# GL3520.net
KiCad netlist of a schematic drawn in Altium Designer
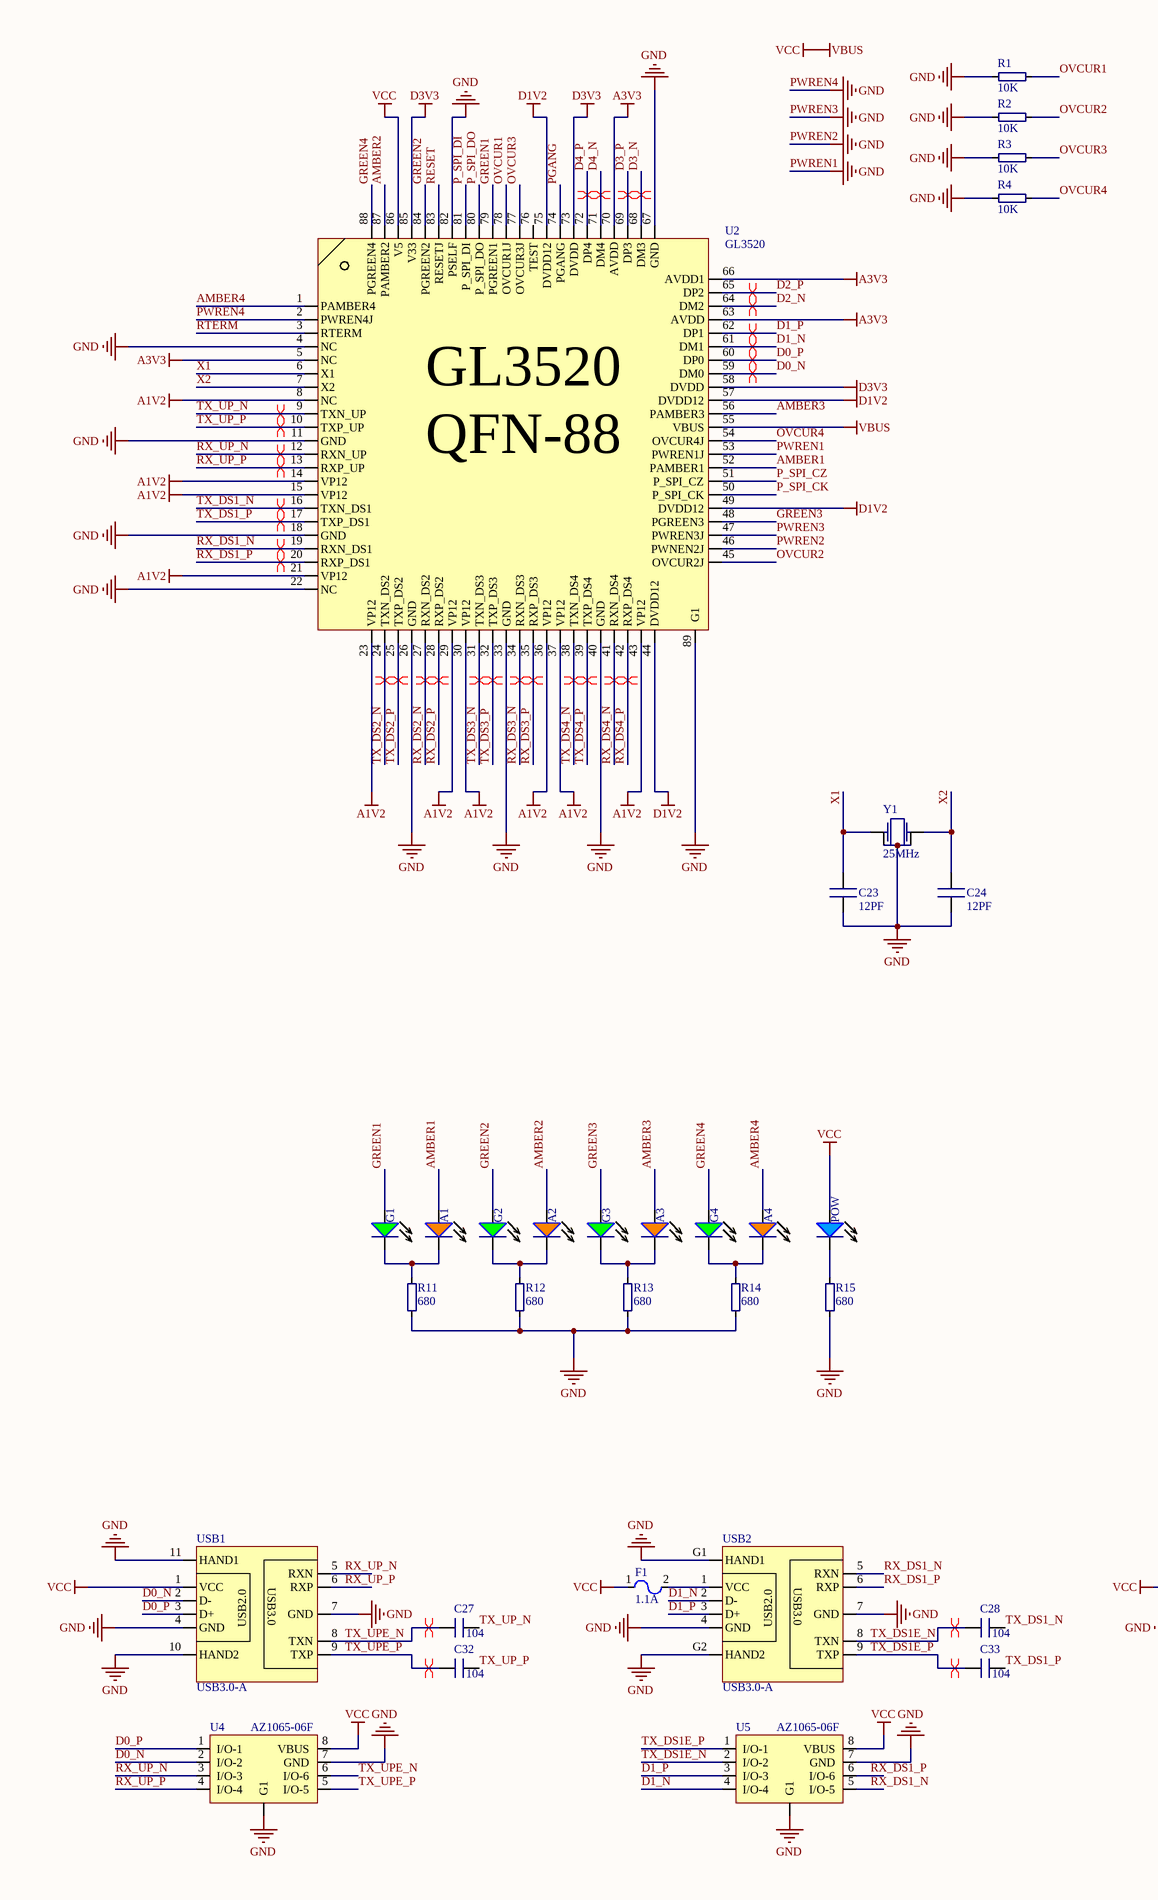
[diagram p0: GL3520.SchDoc, left]
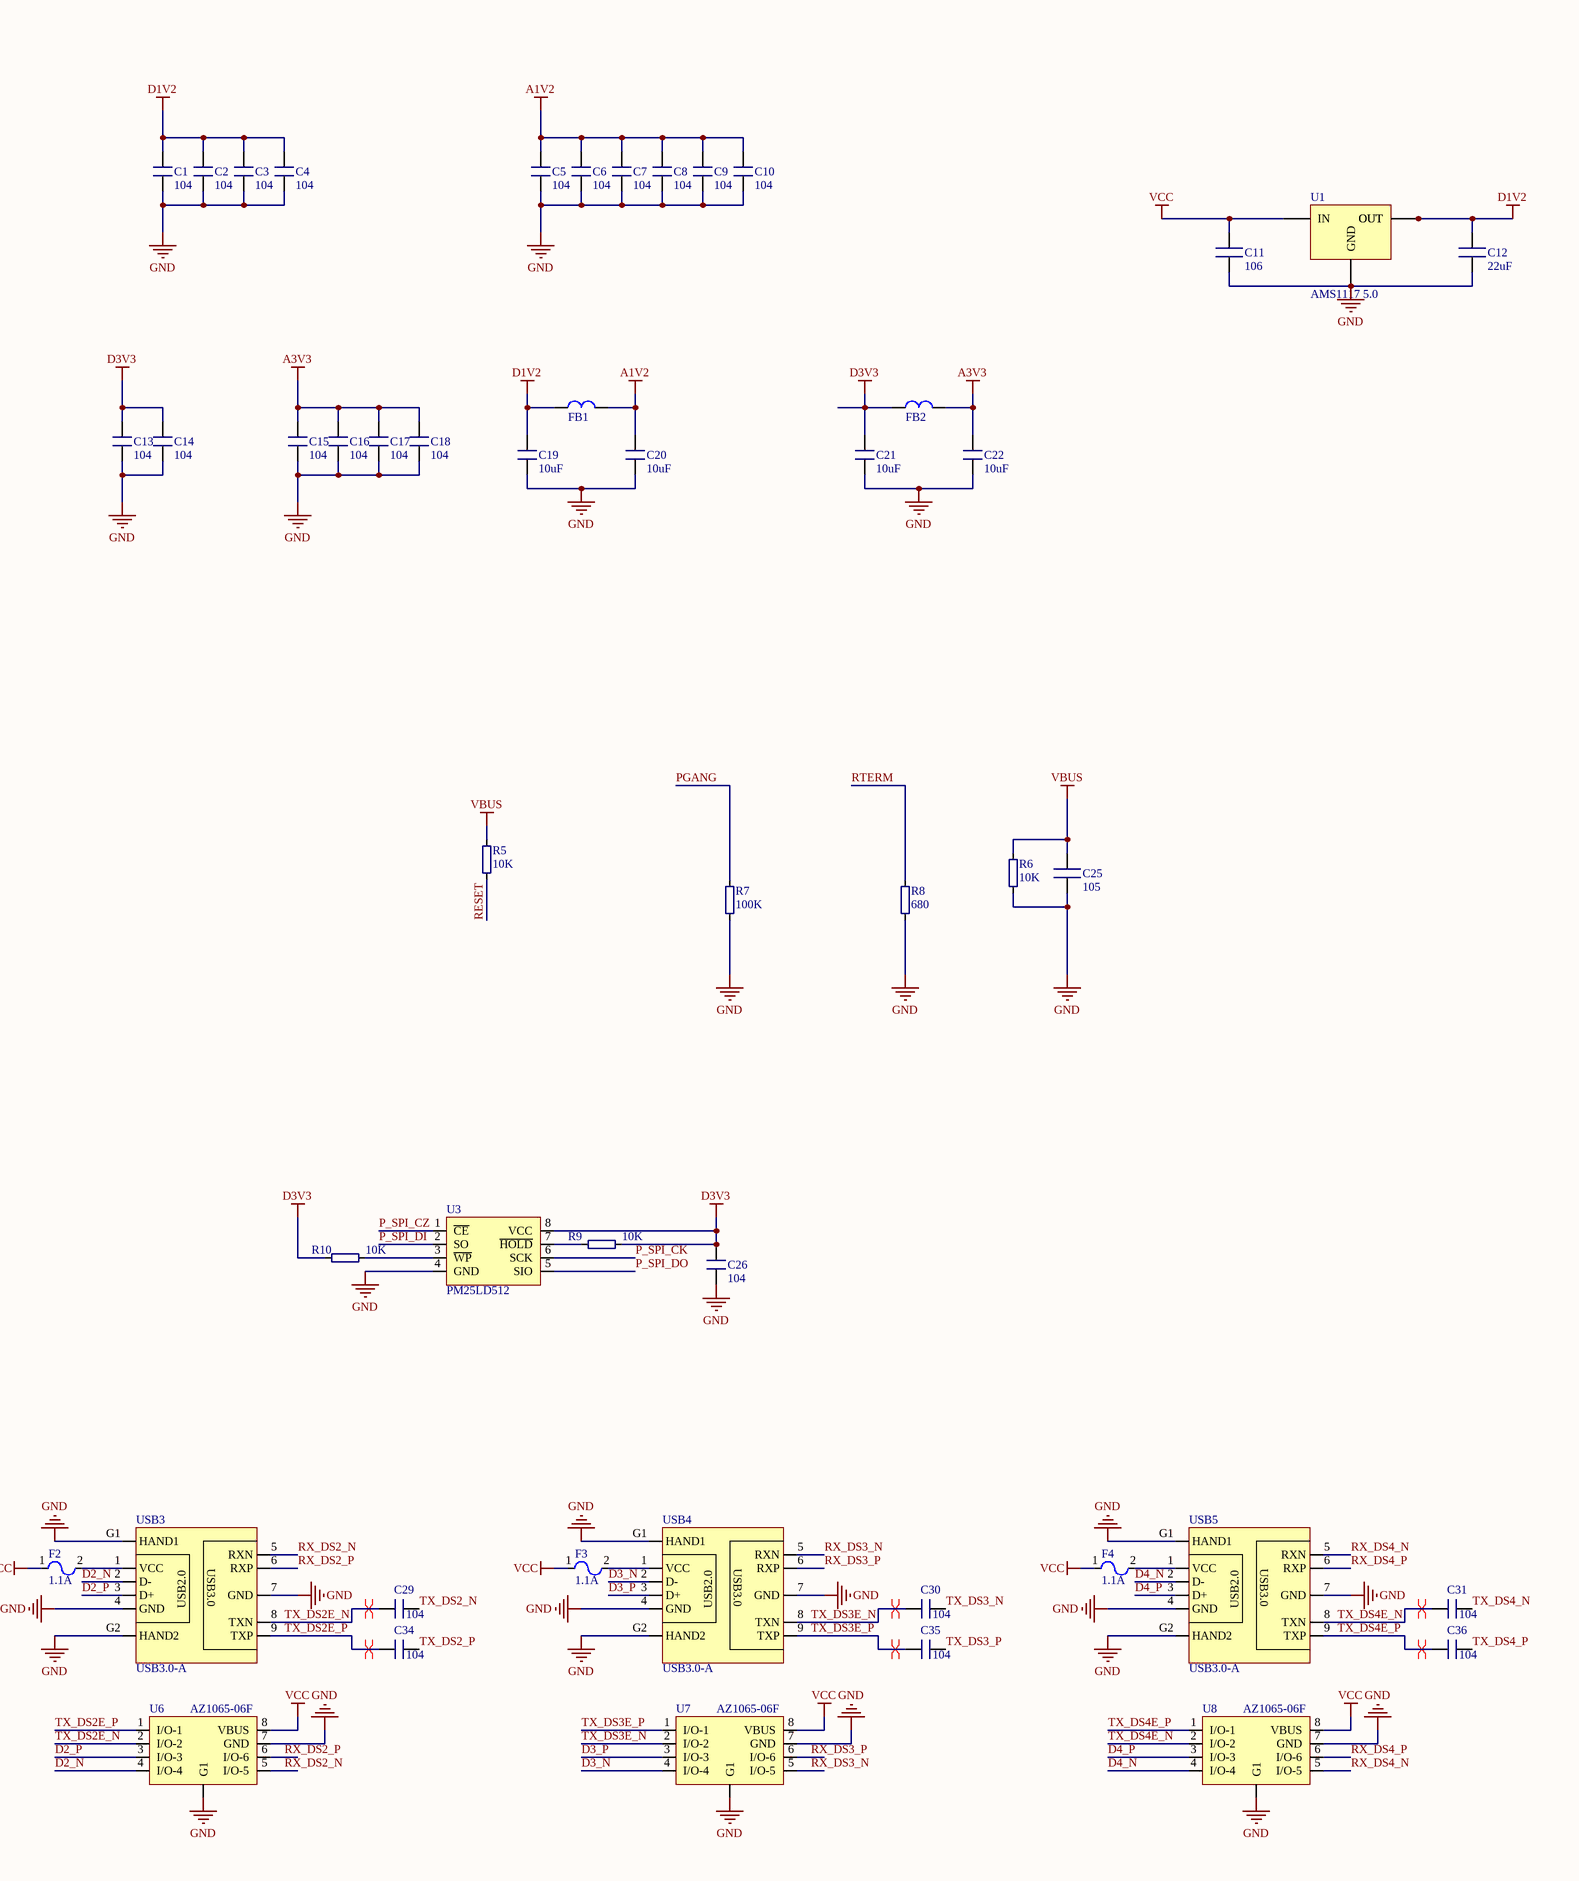
[diagram p1: GL3520.SchDoc, right]

(export (version "E")
  (design (tool "Eeschema 10.0.6"))
  (components
    (comp (ref "A1")
      (value "SMD-LED_Orige")
      (footprint "SMD-LED-0805Y")
      (libsource (lib "arduino") (part "SMD-LED_Orige"))
    )
    (comp (ref "A2")
      (value "SMD-LED_Orige")
      (footprint "SMD-LED-0805Y")
      (libsource (lib "arduino") (part "SMD-LED_Orige"))
    )
    (comp (ref "A3")
      (value "SMD-LED_Orige")
      (footprint "SMD-LED-0805Y")
      (libsource (lib "arduino") (part "SMD-LED_Orige"))
    )
    (comp (ref "A4")
      (value "SMD-LED_Orige")
      (footprint "SMD-LED-0805Y")
      (libsource (lib "arduino") (part "SMD-LED_Orige"))
    )
    (comp (ref "C1") (value "104") (footprint "SMD-C-0201") (libsource (lib "arduino") (part "SMD-C-0201")))
    (comp (ref "C2") (value "104") (footprint "SMD-C-0201") (libsource (lib "arduino") (part "SMD-C-0201")))
    (comp (ref "C3") (value "104") (footprint "SMD-C-0201") (libsource (lib "arduino") (part "SMD-C-0201")))
    (comp (ref "C4") (value "104") (footprint "SMD-C-0201") (libsource (lib "arduino") (part "SMD-C-0201")))
    (comp (ref "C5") (value "104") (footprint "SMD-C-0201") (libsource (lib "arduino") (part "SMD-C-0201")))
    (comp (ref "C6") (value "104") (footprint "SMD-C-0201") (libsource (lib "arduino") (part "SMD-C-0201")))
    (comp (ref "C7") (value "104") (footprint "SMD-C-0201") (libsource (lib "arduino") (part "SMD-C-0201")))
    (comp (ref "C8") (value "104") (footprint "SMD-C-0201") (libsource (lib "arduino") (part "SMD-C-0201")))
    (comp (ref "C9") (value "104") (footprint "SMD-C-0201") (libsource (lib "arduino") (part "SMD-C-0201")))
    (comp (ref "C10") (value "104") (footprint "SMD-C-0201") (libsource (lib "arduino") (part "SMD-C-0201")))
    (comp (ref "C11")
      (value "106")
      (footprint "SMD-C-0805")
      (fields (field (name "Comment") "SMD-C-0805"))
      (libsource (lib "") (part "SMD-C-0805_1"))
    )
    (comp (ref "C12")
      (value "22uF")
      (footprint "SMD-C-0805")
      (fields (field (name "Comment") "SMD-C-0805"))
      (libsource (lib "") (part "SMD-C-0805_1"))
    )
    (comp (ref "C13") (value "104") (footprint "SMD-C-0201") (libsource (lib "arduino") (part "SMD-C-0201")))
    (comp (ref "C14") (value "104") (footprint "SMD-C-0201") (libsource (lib "arduino") (part "SMD-C-0201")))
    (comp (ref "C15") (value "104") (footprint "SMD-C-0201") (libsource (lib "arduino") (part "SMD-C-0201")))
    (comp (ref "C16") (value "104") (footprint "SMD-C-0201") (libsource (lib "arduino") (part "SMD-C-0201")))
    (comp (ref "C17") (value "104") (footprint "SMD-C-0201") (libsource (lib "arduino") (part "SMD-C-0201")))
    (comp (ref "C18") (value "104") (footprint "SMD-C-0201") (libsource (lib "arduino") (part "SMD-C-0201")))
    (comp (ref "C19")
      (value "10uF")
      (footprint "SMD-C-0805")
      (description "贴片瓷片电容")
      (libsource (lib "arduino") (part "SMD-C-0805"))
    )
    (comp (ref "C20")
      (value "10uF")
      (footprint "SMD-C-0805")
      (description "贴片瓷片电容")
      (libsource (lib "arduino") (part "SMD-C-0805"))
    )
    (comp (ref "C21")
      (value "10uF")
      (footprint "SMD-C-0805")
      (description "贴片瓷片电容")
      (libsource (lib "arduino") (part "SMD-C-0805"))
    )
    (comp (ref "C22")
      (value "10uF")
      (footprint "SMD-C-0805")
      (description "贴片瓷片电容")
      (libsource (lib "arduino") (part "SMD-C-0805"))
    )
    (comp (ref "C23")
      (value "12PF")
      (footprint "SMD-C-0805")
      (fields (field (name "Comment") "SMD-C-0805"))
      (libsource (lib "") (part "SMD-C-0805_1"))
    )
    (comp (ref "C24")
      (value "12PF")
      (footprint "SMD-C-0805")
      (fields (field (name "Comment") "SMD-C-0805"))
      (libsource (lib "") (part "SMD-C-0805_1"))
    )
    (comp (ref "C25")
      (value "105")
      (footprint "SMD-C-0805")
      (fields (field (name "Comment") "SMD-C-0805"))
      (libsource (lib "") (part "SMD-C-0805_1"))
    )
    (comp (ref "C26")
      (value "104")
      (footprint "SMD-C-0805")
      (description "贴片瓷片电容")
      (libsource (lib "arduino") (part "SMD-C-0805"))
    )
    (comp (ref "C27") (value "104") (footprint "SMD-C-0201") (libsource (lib "arduino") (part "SMD-C-0201")))
    (comp (ref "C28") (value "104") (footprint "SMD-C-0201") (libsource (lib "arduino") (part "SMD-C-0201")))
    (comp (ref "C29") (value "104") (footprint "SMD-C-0201") (libsource (lib "arduino") (part "SMD-C-0201")))
    (comp (ref "C30") (value "104") (footprint "SMD-C-0201") (libsource (lib "arduino") (part "SMD-C-0201")))
    (comp (ref "C31") (value "104") (footprint "SMD-C-0201") (libsource (lib "arduino") (part "SMD-C-0201")))
    (comp (ref "C32") (value "104") (footprint "SMD-C-0201") (libsource (lib "arduino") (part "SMD-C-0201")))
    (comp (ref "C33") (value "104") (footprint "SMD-C-0201") (libsource (lib "arduino") (part "SMD-C-0201")))
    (comp (ref "C34") (value "104") (footprint "SMD-C-0201") (libsource (lib "arduino") (part "SMD-C-0201")))
    (comp (ref "C35") (value "104") (footprint "SMD-C-0201") (libsource (lib "arduino") (part "SMD-C-0201")))
    (comp (ref "C36") (value "104") (footprint "SMD-C-0201") (libsource (lib "arduino") (part "SMD-C-0201")))
    (comp (ref "F1")
      (value "1.1A")
      (footprint "SMD-F-0805")
      (description "保险丝贴片自恢复")
      (libsource (lib "arduino") (part "SMD-F-0805"))
    )
    (comp (ref "F2")
      (value "1.1A")
      (footprint "SMD-F-0805")
      (description "保险丝贴片自恢复")
      (libsource (lib "arduino") (part "SMD-F-0805"))
    )
    (comp (ref "F3")
      (value "1.1A")
      (footprint "SMD-F-0805")
      (description "保险丝贴片自恢复")
      (libsource (lib "arduino") (part "SMD-F-0805"))
    )
    (comp (ref "F4")
      (value "1.1A")
      (footprint "SMD-F-0805")
      (description "保险丝贴片自恢复")
      (libsource (lib "arduino") (part "SMD-F-0805"))
    )
    (comp (ref "FB1")
      (value "XXuH")
      (footprint "SMD-L-0805")
      (description "磁珠")
      (libsource (lib "arduino") (part "SMD-L-0805"))
    )
    (comp (ref "FB2")
      (value "XXuH")
      (footprint "SMD-L-0805")
      (description "磁珠")
      (libsource (lib "arduino") (part "SMD-L-0805"))
    )
    (comp (ref "G1")
      (value "SMD-LED_Green")
      (footprint "SMD-LED-0805G")
      (libsource (lib "arduino") (part "SMD-LED_Green"))
    )
    (comp (ref "G2")
      (value "SMD-LED_Green")
      (footprint "SMD-LED-0805G")
      (libsource (lib "arduino") (part "SMD-LED_Green"))
    )
    (comp (ref "G3")
      (value "SMD-LED_Green")
      (footprint "SMD-LED-0805G")
      (libsource (lib "arduino") (part "SMD-LED_Green"))
    )
    (comp (ref "G4")
      (value "SMD-LED_Green")
      (footprint "SMD-LED-0805G")
      (libsource (lib "arduino") (part "SMD-LED_Green"))
    )
    (comp (ref "POW")
      (value "SMD-LED_Blue")
      (footprint "SMD-LED-0805B")
      (libsource (lib "arduino") (part "SMD-LED_Blue"))
    )
    (comp (ref "R1") (value "10K") (footprint "SMD-R-0805") (libsource (lib "arduino") (part "SMD-R-0805")))
    (comp (ref "R2") (value "10K") (footprint "SMD-R-0805") (libsource (lib "arduino") (part "SMD-R-0805")))
    (comp (ref "R3") (value "10K") (footprint "SMD-R-0805") (libsource (lib "arduino") (part "SMD-R-0805")))
    (comp (ref "R4") (value "10K") (footprint "SMD-R-0805") (libsource (lib "arduino") (part "SMD-R-0805")))
    (comp (ref "R5") (value "10K") (footprint "SMD-R-0805") (libsource (lib "arduino") (part "SMD-R-0805")))
    (comp (ref "R6") (value "10K") (footprint "SMD-R-0805") (libsource (lib "arduino") (part "SMD-R-0805")))
    (comp (ref "R7") (value "100K") (footprint "SMD-R-0805") (libsource (lib "arduino") (part "SMD-R-0805")))
    (comp (ref "R8") (value "680") (footprint "SMD-R-0805") (libsource (lib "arduino") (part "SMD-R-0805")))
    (comp (ref "R9") (value "10K") (footprint "SMD-R-0805") (libsource (lib "arduino") (part "SMD-R-0805")))
    (comp (ref "R10") (value "10K") (footprint "SMD-R-0805") (libsource (lib "arduino") (part "SMD-R-0805")))
    (comp (ref "R11") (value "680") (footprint "SMD-R-0805") (libsource (lib "arduino") (part "SMD-R-0805")))
    (comp (ref "R12") (value "680") (footprint "SMD-R-0805") (libsource (lib "arduino") (part "SMD-R-0805")))
    (comp (ref "R13") (value "680") (footprint "SMD-R-0805") (libsource (lib "arduino") (part "SMD-R-0805")))
    (comp (ref "R14") (value "680") (footprint "SMD-R-0805") (libsource (lib "arduino") (part "SMD-R-0805")))
    (comp (ref "R15") (value "680") (footprint "SMD-R-0805") (libsource (lib "arduino") (part "SMD-R-0805")))
    (comp (ref "U1")
      (value "AMS1117 5.0")
      (footprint "SOT-223")
      (libsource (lib "arduino") (part "SMD-IC-AMS1117"))
    )
    (comp (ref "U2")
      (value "GL3520")
      (footprint "SMD-QFN88")
      (description "USB3.0 HUB controller")
      (libsource (lib "arduino") (part "SMD-IC-GL3520-QFN88"))
    )
    (comp (ref "U3")
      (value "PM25LD512")
      (footprint "SMD-SOP8")
      (description "flash芯片")
      (libsource (lib "arduino") (part "SMD-IC-PM25LD512"))
    )
    (comp (ref "U4")
      (value "AZ1065-06F")
      (footprint "SMD-U-DFN4120P10E")
      (description "TVS阵列保护")
      (libsource (lib "arduino") (part "SMD-IC-AZ1065-06F"))
    )
    (comp (ref "U5")
      (value "AZ1065-06F")
      (footprint "SMD-U-DFN4120P10E")
      (description "TVS阵列保护")
      (libsource (lib "arduino") (part "SMD-IC-AZ1065-06F"))
    )
    (comp (ref "U6")
      (value "AZ1065-06F")
      (footprint "SMD-U-DFN4120P10E")
      (description "TVS阵列保护")
      (libsource (lib "arduino") (part "SMD-IC-AZ1065-06F"))
    )
    (comp (ref "U7")
      (value "AZ1065-06F")
      (footprint "SMD-U-DFN4120P10E")
      (description "TVS阵列保护")
      (libsource (lib "arduino") (part "SMD-IC-AZ1065-06F"))
    )
    (comp (ref "U8")
      (value "AZ1065-06F")
      (footprint "SMD-U-DFN4120P10E")
      (description "TVS阵列保护")
      (libsource (lib "arduino") (part "SMD-IC-AZ1065-06F"))
    )
    (comp (ref "USB1")
      (value "USB3.0-A")
      (footprint "DIP-USB3.0-AF90")
      (libsource (lib "arduino") (part "DIP-USB3.-AF90"))
    )
    (comp (ref "USB2")
      (value "USB3.0-A")
      (footprint "DIP-USB3.0-M-LI")
      (libsource (lib "arduino") (part "DIP-USB3.0"))
    )
    (comp (ref "USB3")
      (value "USB3.0-A")
      (footprint "DIP-USB3.0-M-LI")
      (libsource (lib "arduino") (part "DIP-USB3.0"))
    )
    (comp (ref "USB4")
      (value "USB3.0-A")
      (footprint "DIP-USB3.0-M-LI")
      (libsource (lib "arduino") (part "DIP-USB3.0"))
    )
    (comp (ref "USB5")
      (value "USB3.0-A")
      (footprint "DIP-USB3.0-M-LI")
      (libsource (lib "arduino") (part "DIP-USB3.0"))
    )
    (comp (ref "Y1")
      (value "25MHz")
      (footprint "SMD-XTAL-3225")
      (description "晶振")
      (fields (field (name "Comment") "SMT-XTAL-3225"))
      (libsource (lib "arduino") (part "SMT-XTAL-3225"))
    )
  )
  (nets
    (net (code "1") (name "/AMBER1") (class "Default")
      (node (ref "A1") (pin "1") (pinfunction "1_1") (pintype "passive"))
      (node (ref "U2") (pin "52") (pinfunction "PAMBER1_52") (pintype "passive"))
    )
    (net (code "2") (name "/AMBER2") (class "Default")
      (node (ref "A2") (pin "1") (pinfunction "1_1") (pintype "passive"))
      (node (ref "U2") (pin "87") (pinfunction "PAMBER2_87") (pintype "passive"))
    )
    (net (code "3") (name "/AMBER3") (class "Default")
      (node (ref "A3") (pin "1") (pinfunction "1_1") (pintype "passive"))
      (node (ref "U2") (pin "56") (pinfunction "PAMBER3_56") (pintype "passive"))
    )
    (net (code "4") (name "/AMBER4") (class "Default")
      (node (ref "A4") (pin "1") (pinfunction "1_1") (pintype "passive"))
      (node (ref "U2") (pin "1") (pinfunction "PAMBER4_1") (pintype "passive"))
    )
    (net (code "5") (name "/D0_N") (class "Default")
      (node (ref "U2") (pin "59") (pinfunction "DM0_59") (pintype "passive"))
      (node (ref "U4") (pin "2") (pinfunction "I/O-2_2") (pintype "passive"))
      (node (ref "USB1") (pin "2") (pinfunction "D-_2") (pintype "passive"))
    )
    (net (code "6") (name "/D0_P") (class "Default")
      (node (ref "U2") (pin "60") (pinfunction "DP0_60") (pintype "passive"))
      (node (ref "U4") (pin "1") (pinfunction "I/O-1_1") (pintype "passive"))
      (node (ref "USB1") (pin "3") (pinfunction "D+_3") (pintype "passive"))
    )
    (net (code "7") (name "/D1_N") (class "Default")
      (node (ref "U2") (pin "61") (pinfunction "DM1_61") (pintype "passive"))
      (node (ref "U5") (pin "4") (pinfunction "I/O-4_4") (pintype "passive"))
      (node (ref "USB2") (pin "2") (pinfunction "D-_2") (pintype "passive"))
    )
    (net (code "8") (name "/D1_P") (class "Default")
      (node (ref "U2") (pin "62") (pinfunction "DP1_62") (pintype "passive"))
      (node (ref "U5") (pin "3") (pinfunction "I/O-3_3") (pintype "passive"))
      (node (ref "USB2") (pin "3") (pinfunction "D+_3") (pintype "passive"))
    )
    (net (code "9") (name "/D2_N") (class "Default")
      (node (ref "U2") (pin "64") (pinfunction "DM2_64") (pintype "passive"))
      (node (ref "U6") (pin "4") (pinfunction "I/O-4_4") (pintype "passive"))
      (node (ref "USB3") (pin "2") (pinfunction "D-_2") (pintype "passive"))
    )
    (net (code "10") (name "/D2_P") (class "Default")
      (node (ref "U2") (pin "65") (pinfunction "DP2_65") (pintype "passive"))
      (node (ref "U6") (pin "3") (pinfunction "I/O-3_3") (pintype "passive"))
      (node (ref "USB3") (pin "3") (pinfunction "D+_3") (pintype "passive"))
    )
    (net (code "11") (name "/D3_N") (class "Default")
      (node (ref "U2") (pin "68") (pinfunction "DM3_68") (pintype "passive"))
      (node (ref "U7") (pin "4") (pinfunction "I/O-4_4") (pintype "passive"))
      (node (ref "USB4") (pin "2") (pinfunction "D-_2") (pintype "passive"))
    )
    (net (code "12") (name "/D3_P") (class "Default")
      (node (ref "U2") (pin "69") (pinfunction "DP3_69") (pintype "passive"))
      (node (ref "U7") (pin "3") (pinfunction "I/O-3_3") (pintype "passive"))
      (node (ref "USB4") (pin "3") (pinfunction "D+_3") (pintype "passive"))
    )
    (net (code "13") (name "/D4_N") (class "Default")
      (node (ref "U2") (pin "71") (pinfunction "DM4_71") (pintype "passive"))
      (node (ref "U8") (pin "4") (pinfunction "I/O-4_4") (pintype "passive"))
      (node (ref "USB5") (pin "2") (pinfunction "D-_2") (pintype "passive"))
    )
    (net (code "14") (name "/D4_P") (class "Default")
      (node (ref "U2") (pin "72") (pinfunction "DP4_72") (pintype "passive"))
      (node (ref "U8") (pin "3") (pinfunction "I/O-3_3") (pintype "passive"))
      (node (ref "USB5") (pin "3") (pinfunction "D+_3") (pintype "passive"))
    )
    (net (code "15") (name "/GREEN1") (class "Default")
      (node (ref "G1") (pin "1") (pinfunction "1_1") (pintype "passive"))
      (node (ref "U2") (pin "79") (pinfunction "PGREEN1_79") (pintype "passive"))
    )
    (net (code "16") (name "/GREEN2") (class "Default")
      (node (ref "G2") (pin "1") (pinfunction "1_1") (pintype "passive"))
      (node (ref "U2") (pin "84") (pinfunction "PGREEN2_84") (pintype "passive"))
    )
    (net (code "17") (name "/GREEN3") (class "Default")
      (node (ref "G3") (pin "1") (pinfunction "1_1") (pintype "passive"))
      (node (ref "U2") (pin "48") (pinfunction "PGREEN3_48") (pintype "passive"))
    )
    (net (code "18") (name "/GREEN4") (class "Default")
      (node (ref "G4") (pin "1") (pinfunction "1_1") (pintype "passive"))
      (node (ref "U2") (pin "88") (pinfunction "PGREEN4_88") (pintype "passive"))
    )
    (net (code "19") (name "/OVCUR1") (class "Default")
      (node (ref "R1") (pin "2") (pintype "passive"))
      (node (ref "U2") (pin "78") (pinfunction "OVCUR1J_78") (pintype "passive"))
    )
    (net (code "20") (name "/OVCUR2") (class "Default")
      (node (ref "R2") (pin "2") (pintype "passive"))
      (node (ref "U2") (pin "45") (pinfunction "OVCUR2J_45") (pintype "passive"))
    )
    (net (code "21") (name "/OVCUR3") (class "Default")
      (node (ref "R3") (pin "2") (pintype "passive"))
      (node (ref "U2") (pin "77") (pinfunction "OVCUR3J_77") (pintype "passive"))
    )
    (net (code "22") (name "/OVCUR4") (class "Default")
      (node (ref "R4") (pin "2") (pintype "passive"))
      (node (ref "U2") (pin "54") (pinfunction "OVCUR4J_54") (pintype "passive"))
    )
    (net (code "23") (name "/PGANG") (class "Default")
      (node (ref "R7") (pin "2") (pintype "passive"))
      (node (ref "U2") (pin "74") (pinfunction "PGANG_74") (pintype "passive"))
    )
    (net (code "24") (name "/P_SPI_CK") (class "Default")
      (node (ref "U2") (pin "50") (pinfunction "P_SPI_CK_50") (pintype "passive"))
      (node (ref "U3") (pin "6") (pinfunction "SCK_6") (pintype "passive"))
    )
    (net (code "25") (name "/P_SPI_CZ") (class "Default")
      (node (ref "U2") (pin "51") (pinfunction "P_SPI_CZ_51") (pintype "passive"))
      (node (ref "U3") (pin "1") (pinfunction "~{CE}_1") (pintype "passive"))
    )
    (net (code "26") (name "/P_SPI_DI") (class "Default")
      (node (ref "U2") (pin "81") (pinfunction "P_SPI_DI_81") (pintype "passive"))
      (node (ref "U3") (pin "2") (pinfunction "SO_2") (pintype "passive"))
    )
    (net (code "27") (name "/P_SPI_DO") (class "Default")
      (node (ref "U2") (pin "80") (pinfunction "P_SPI_DO_80") (pintype "passive"))
      (node (ref "U3") (pin "5") (pinfunction "SIO_5") (pintype "passive"))
    )
    (net (code "28") (name "/RESET") (class "Default")
      (node (ref "R5") (pin "1") (pintype "passive"))
      (node (ref "U2") (pin "83") (pinfunction "RESETJ_83") (pintype "passive"))
    )
    (net (code "29") (name "/RTERM") (class "Default")
      (node (ref "R8") (pin "2") (pintype "passive"))
      (node (ref "U2") (pin "3") (pinfunction "RTERM_3") (pintype "passive"))
    )
    (net (code "30") (name "/RX_DS1_N") (class "Default")
      (node (ref "U2") (pin "19") (pinfunction "RXN_DS1_19") (pintype "passive"))
      (node (ref "U5") (pin "5") (pinfunction "I/O-5_5") (pintype "passive"))
      (node (ref "USB2") (pin "5") (pinfunction "RXN_5") (pintype "passive"))
    )
    (net (code "31") (name "/RX_DS1_P") (class "Default")
      (node (ref "U2") (pin "20") (pinfunction "RXP_DS1_20") (pintype "passive"))
      (node (ref "U5") (pin "6") (pinfunction "I/O-6_6") (pintype "passive"))
      (node (ref "USB2") (pin "6") (pinfunction "RXP_6") (pintype "passive"))
    )
    (net (code "32") (name "/RX_DS2_N") (class "Default")
      (node (ref "U2") (pin "27") (pinfunction "RXN_DS2_27") (pintype "passive"))
      (node (ref "U6") (pin "5") (pinfunction "I/O-5_5") (pintype "passive"))
      (node (ref "USB3") (pin "5") (pinfunction "RXN_5") (pintype "passive"))
    )
    (net (code "33") (name "/RX_DS2_P") (class "Default")
      (node (ref "U2") (pin "28") (pinfunction "RXP_DS2_28") (pintype "passive"))
      (node (ref "U6") (pin "6") (pinfunction "I/O-6_6") (pintype "passive"))
      (node (ref "USB3") (pin "6") (pinfunction "RXP_6") (pintype "passive"))
    )
    (net (code "34") (name "/RX_DS3_N") (class "Default")
      (node (ref "U2") (pin "34") (pinfunction "RXN_DS3_34") (pintype "passive"))
      (node (ref "U7") (pin "5") (pinfunction "I/O-5_5") (pintype "passive"))
      (node (ref "USB4") (pin "5") (pinfunction "RXN_5") (pintype "passive"))
    )
    (net (code "35") (name "/RX_DS3_P") (class "Default")
      (node (ref "U2") (pin "35") (pinfunction "RXP_DS3_35") (pintype "passive"))
      (node (ref "U7") (pin "6") (pinfunction "I/O-6_6") (pintype "passive"))
      (node (ref "USB4") (pin "6") (pinfunction "RXP_6") (pintype "passive"))
    )
    (net (code "36") (name "/RX_DS4_N") (class "Default")
      (node (ref "U2") (pin "41") (pinfunction "RXN_DS4_41") (pintype "passive"))
      (node (ref "U8") (pin "5") (pinfunction "I/O-5_5") (pintype "passive"))
      (node (ref "USB5") (pin "5") (pinfunction "RXN_5") (pintype "passive"))
    )
    (net (code "37") (name "/RX_DS4_P") (class "Default")
      (node (ref "U2") (pin "42") (pinfunction "RXP_DS4_42") (pintype "passive"))
      (node (ref "U8") (pin "6") (pinfunction "I/O-6_6") (pintype "passive"))
      (node (ref "USB5") (pin "6") (pinfunction "RXP_6") (pintype "passive"))
    )
    (net (code "38") (name "/RX_UP_N") (class "Default")
      (node (ref "U2") (pin "12") (pinfunction "RXN_UP_12") (pintype "passive"))
      (node (ref "U4") (pin "3") (pinfunction "I/O-3_3") (pintype "passive"))
      (node (ref "USB1") (pin "5") (pinfunction "RXN_5") (pintype "passive"))
    )
    (net (code "39") (name "/RX_UP_P") (class "Default")
      (node (ref "U2") (pin "13") (pinfunction "RXP_UP_13") (pintype "passive"))
      (node (ref "U4") (pin "4") (pinfunction "I/O-4_4") (pintype "passive"))
      (node (ref "USB1") (pin "6") (pinfunction "RXP_6") (pintype "passive"))
    )
    (net (code "40") (name "/TX_DS1E_N") (class "Default")
      (node (ref "C28") (pin "1") (pintype "passive"))
      (node (ref "U5") (pin "2") (pinfunction "I/O-2_2") (pintype "passive"))
      (node (ref "USB2") (pin "8") (pinfunction "TXN_8") (pintype "passive"))
    )
    (net (code "41") (name "/TX_DS1E_P") (class "Default")
      (node (ref "C33") (pin "1") (pintype "passive"))
      (node (ref "U5") (pin "1") (pinfunction "I/O-1_1") (pintype "passive"))
      (node (ref "USB2") (pin "9") (pinfunction "TXP_9") (pintype "passive"))
    )
    (net (code "42") (name "/TX_DS1_N") (class "Default")
      (node (ref "C28") (pin "2") (pintype "passive"))
      (node (ref "U2") (pin "16") (pinfunction "TXN_DS1_16") (pintype "passive"))
    )
    (net (code "43") (name "/TX_DS1_P") (class "Default")
      (node (ref "C33") (pin "2") (pintype "passive"))
      (node (ref "U2") (pin "17") (pinfunction "TXP_DS1_17") (pintype "passive"))
    )
    (net (code "44") (name "/TX_DS2E_N") (class "Default")
      (node (ref "C29") (pin "1") (pintype "passive"))
      (node (ref "U6") (pin "2") (pinfunction "I/O-2_2") (pintype "passive"))
      (node (ref "USB3") (pin "8") (pinfunction "TXN_8") (pintype "passive"))
    )
    (net (code "45") (name "/TX_DS2E_P") (class "Default")
      (node (ref "C34") (pin "1") (pintype "passive"))
      (node (ref "U6") (pin "1") (pinfunction "I/O-1_1") (pintype "passive"))
      (node (ref "USB3") (pin "9") (pinfunction "TXP_9") (pintype "passive"))
    )
    (net (code "46") (name "/TX_DS2_N") (class "Default")
      (node (ref "C29") (pin "2") (pintype "passive"))
      (node (ref "U2") (pin "24") (pinfunction "TXN_DS2_24") (pintype "passive"))
    )
    (net (code "47") (name "/TX_DS2_P") (class "Default")
      (node (ref "C34") (pin "2") (pintype "passive"))
      (node (ref "U2") (pin "25") (pinfunction "TXP_DS2_25") (pintype "passive"))
    )
    (net (code "48") (name "/TX_DS3E_N") (class "Default")
      (node (ref "C30") (pin "1") (pintype "passive"))
      (node (ref "U7") (pin "2") (pinfunction "I/O-2_2") (pintype "passive"))
      (node (ref "USB4") (pin "8") (pinfunction "TXN_8") (pintype "passive"))
    )
    (net (code "49") (name "/TX_DS3E_P") (class "Default")
      (node (ref "C35") (pin "1") (pintype "passive"))
      (node (ref "U7") (pin "1") (pinfunction "I/O-1_1") (pintype "passive"))
      (node (ref "USB4") (pin "9") (pinfunction "TXP_9") (pintype "passive"))
    )
    (net (code "50") (name "/TX_DS3_N") (class "Default")
      (node (ref "C30") (pin "2") (pintype "passive"))
      (node (ref "U2") (pin "31") (pinfunction "TXN_DS3_31") (pintype "passive"))
    )
    (net (code "51") (name "/TX_DS3_P") (class "Default")
      (node (ref "C35") (pin "2") (pintype "passive"))
      (node (ref "U2") (pin "32") (pinfunction "TXP_DS3_32") (pintype "passive"))
    )
    (net (code "52") (name "/TX_DS4E_N") (class "Default")
      (node (ref "C31") (pin "1") (pintype "passive"))
      (node (ref "U8") (pin "2") (pinfunction "I/O-2_2") (pintype "passive"))
      (node (ref "USB5") (pin "8") (pinfunction "TXN_8") (pintype "passive"))
    )
    (net (code "53") (name "/TX_DS4E_P") (class "Default")
      (node (ref "C36") (pin "1") (pintype "passive"))
      (node (ref "U8") (pin "1") (pinfunction "I/O-1_1") (pintype "passive"))
      (node (ref "USB5") (pin "9") (pinfunction "TXP_9") (pintype "passive"))
    )
    (net (code "54") (name "/TX_DS4_N") (class "Default")
      (node (ref "C31") (pin "2") (pintype "passive"))
      (node (ref "U2") (pin "38") (pinfunction "TXN_DS4_38") (pintype "passive"))
    )
    (net (code "55") (name "/TX_DS4_P") (class "Default")
      (node (ref "C36") (pin "2") (pintype "passive"))
      (node (ref "U2") (pin "39") (pinfunction "TXP_DS4_39") (pintype "passive"))
    )
    (net (code "56") (name "/TX_UPE_N") (class "Default")
      (node (ref "C27") (pin "1") (pintype "passive"))
      (node (ref "U4") (pin "6") (pinfunction "I/O-6_6") (pintype "passive"))
      (node (ref "USB1") (pin "8") (pinfunction "TXN_8") (pintype "passive"))
    )
    (net (code "57") (name "/TX_UPE_P") (class "Default")
      (node (ref "C32") (pin "1") (pintype "passive"))
      (node (ref "U4") (pin "5") (pinfunction "I/O-5_5") (pintype "passive"))
      (node (ref "USB1") (pin "9") (pinfunction "TXP_9") (pintype "passive"))
    )
    (net (code "58") (name "/TX_UP_N") (class "Default")
      (node (ref "C27") (pin "2") (pintype "passive"))
      (node (ref "U2") (pin "9") (pinfunction "TXN_UP_9") (pintype "passive"))
    )
    (net (code "59") (name "/TX_UP_P") (class "Default")
      (node (ref "C32") (pin "2") (pintype "passive"))
      (node (ref "U2") (pin "10") (pinfunction "TXP_UP_10") (pintype "passive"))
    )
    (net (code "60") (name "/X1") (class "Default")
      (node (ref "C23") (pin "2") (pintype "passive"))
      (node (ref "U2") (pin "6") (pinfunction "X1_6") (pintype "passive"))
      (node (ref "Y1") (pin "1") (pinfunction "1_1") (pintype "passive"))
    )
    (net (code "61") (name "/X2") (class "Default")
      (node (ref "C24") (pin "2") (pintype "passive"))
      (node (ref "U2") (pin "7") (pinfunction "X2_7") (pintype "passive"))
      (node (ref "Y1") (pin "3") (pinfunction "3_3") (pintype "passive"))
    )
    (net (code "62") (name "A1V2") (class "Default")
      (node (ref "C10") (pin "2") (pintype "passive"))
      (node (ref "C20") (pin "2") (pintype "passive"))
      (node (ref "C5") (pin "2") (pintype "passive"))
      (node (ref "C6") (pin "2") (pintype "passive"))
      (node (ref "C7") (pin "2") (pintype "passive"))
      (node (ref "C8") (pin "2") (pintype "passive"))
      (node (ref "C9") (pin "2") (pintype "passive"))
      (node (ref "FB1") (pin "1") (pinfunction "1_1") (pintype "passive"))
      (node (ref "U2") (pin "14") (pinfunction "VP12_14") (pintype "passive"))
      (node (ref "U2") (pin "15") (pinfunction "VP12_15") (pintype "passive"))
      (node (ref "U2") (pin "21") (pinfunction "VP12_21") (pintype "passive"))
      (node (ref "U2") (pin "23") (pinfunction "VP12_23") (pintype "passive"))
      (node (ref "U2") (pin "29") (pinfunction "VP12_29") (pintype "passive"))
      (node (ref "U2") (pin "30") (pinfunction "VP12_30") (pintype "passive"))
      (node (ref "U2") (pin "36") (pinfunction "VP12_36") (pintype "passive"))
      (node (ref "U2") (pin "37") (pinfunction "VP12_37") (pintype "passive"))
      (node (ref "U2") (pin "43") (pinfunction "VP12_43") (pintype "passive"))
      (node (ref "U2") (pin "8") (pinfunction "NC_8") (pintype "passive"))
    )
    (net (code "63") (name "A3V3") (class "Default")
      (node (ref "C15") (pin "2") (pintype "passive"))
      (node (ref "C16") (pin "2") (pintype "passive"))
      (node (ref "C17") (pin "2") (pintype "passive"))
      (node (ref "C18") (pin "2") (pintype "passive"))
      (node (ref "C22") (pin "2") (pintype "passive"))
      (node (ref "FB2") (pin "1") (pinfunction "1_1") (pintype "passive"))
      (node (ref "U2") (pin "5") (pinfunction "NC_5") (pintype "passive"))
      (node (ref "U2") (pin "63") (pinfunction "AVDD_63") (pintype "passive"))
      (node (ref "U2") (pin "66") (pinfunction "AVDD1_66") (pintype "passive"))
      (node (ref "U2") (pin "70") (pinfunction "AVDD_70") (pintype "passive"))
    )
    (net (code "64") (name "D1V2") (class "Default")
      (node (ref "C1") (pin "2") (pintype "passive"))
      (node (ref "C12") (pin "2") (pintype "passive"))
      (node (ref "C19") (pin "2") (pintype "passive"))
      (node (ref "C2") (pin "2") (pintype "passive"))
      (node (ref "C3") (pin "2") (pintype "passive"))
      (node (ref "C4") (pin "2") (pintype "passive"))
      (node (ref "FB1") (pin "2") (pinfunction "2_2") (pintype "passive"))
      (node (ref "U1") (pin "0") (pinfunction "OUT_0") (pintype "passive"))
      (node (ref "U1") (pin "2") (pinfunction "OUT_2") (pintype "passive"))
      (node (ref "U2") (pin "44") (pinfunction "DVDD12_44") (pintype "passive"))
      (node (ref "U2") (pin "49") (pinfunction "DVDD12_49") (pintype "passive"))
      (node (ref "U2") (pin "57") (pinfunction "DVDD12_57") (pintype "passive"))
      (node (ref "U2") (pin "75") (pinfunction "DVDD12_75") (pintype "passive"))
    )
    (net (code "65") (name "D3V3") (class "Default")
      (node (ref "C13") (pin "2") (pintype "passive"))
      (node (ref "C14") (pin "2") (pintype "passive"))
      (node (ref "C21") (pin "2") (pintype "passive"))
      (node (ref "C26") (pin "2") (pintype "passive"))
      (node (ref "FB2") (pin "2") (pinfunction "2_2") (pintype "passive"))
      (node (ref "R10") (pin "1") (pintype "passive"))
      (node (ref "R9") (pin "2") (pintype "passive"))
      (node (ref "U2") (pin "58") (pinfunction "DVDD_58") (pintype "passive"))
      (node (ref "U2") (pin "73") (pinfunction "DVDD_73") (pintype "passive"))
      (node (ref "U2") (pin "85") (pinfunction "V33_85") (pintype "passive"))
      (node (ref "U3") (pin "8") (pinfunction "VCC_8") (pintype "passive"))
    )
    (net (code "66") (name "GND") (class "Default")
      (node (ref "C1") (pin "1") (pintype "passive"))
      (node (ref "C10") (pin "1") (pintype "passive"))
      (node (ref "C11") (pin "1") (pintype "passive"))
      (node (ref "C12") (pin "1") (pintype "passive"))
      (node (ref "C13") (pin "1") (pintype "passive"))
      (node (ref "C14") (pin "1") (pintype "passive"))
      (node (ref "C15") (pin "1") (pintype "passive"))
      (node (ref "C16") (pin "1") (pintype "passive"))
      (node (ref "C17") (pin "1") (pintype "passive"))
      (node (ref "C18") (pin "1") (pintype "passive"))
      (node (ref "C19") (pin "1") (pintype "passive"))
      (node (ref "C2") (pin "1") (pintype "passive"))
      (node (ref "C20") (pin "1") (pintype "passive"))
      (node (ref "C21") (pin "1") (pintype "passive"))
      (node (ref "C22") (pin "1") (pintype "passive"))
      (node (ref "C23") (pin "1") (pintype "passive"))
      (node (ref "C24") (pin "1") (pintype "passive"))
      (node (ref "C25") (pin "1") (pintype "passive"))
      (node (ref "C26") (pin "1") (pintype "passive"))
      (node (ref "C3") (pin "1") (pintype "passive"))
      (node (ref "C4") (pin "1") (pintype "passive"))
      (node (ref "C5") (pin "1") (pintype "passive"))
      (node (ref "C6") (pin "1") (pintype "passive"))
      (node (ref "C7") (pin "1") (pintype "passive"))
      (node (ref "C8") (pin "1") (pintype "passive"))
      (node (ref "C9") (pin "1") (pintype "passive"))
      (node (ref "R1") (pin "1") (pintype "passive"))
      (node (ref "R11") (pin "1") (pintype "passive"))
      (node (ref "R12") (pin "1") (pintype "passive"))
      (node (ref "R13") (pin "1") (pintype "passive"))
      (node (ref "R14") (pin "1") (pintype "passive"))
      (node (ref "R15") (pin "1") (pintype "passive"))
      (node (ref "R2") (pin "1") (pintype "passive"))
      (node (ref "R3") (pin "1") (pintype "passive"))
      (node (ref "R4") (pin "1") (pintype "passive"))
      (node (ref "R6") (pin "1") (pintype "passive"))
      (node (ref "R7") (pin "1") (pintype "passive"))
      (node (ref "R8") (pin "1") (pintype "passive"))
      (node (ref "U1") (pin "1") (pinfunction "GND_1") (pintype "passive"))
      (node (ref "U2") (pin "11") (pinfunction "GND_11") (pintype "passive"))
      (node (ref "U2") (pin "18") (pinfunction "GND_18") (pintype "passive"))
      (node (ref "U2") (pin "2") (pinfunction "PWREN4J_2") (pintype "passive"))
      (node (ref "U2") (pin "22") (pinfunction "NC_22") (pintype "passive"))
      (node (ref "U2") (pin "26") (pinfunction "GND_26") (pintype "passive"))
      (node (ref "U2") (pin "33") (pinfunction "GND_33") (pintype "passive"))
      (node (ref "U2") (pin "4") (pinfunction "NC_4") (pintype "passive"))
      (node (ref "U2") (pin "40") (pinfunction "GND_40") (pintype "passive"))
      (node (ref "U2") (pin "46") (pinfunction "PWNEN2J_46") (pintype "passive"))
      (node (ref "U2") (pin "47") (pinfunction "PWREN3J_47") (pintype "passive"))
      (node (ref "U2") (pin "53") (pinfunction "PWREN1J_53") (pintype "passive"))
      (node (ref "U2") (pin "67") (pinfunction "GND_67") (pintype "passive"))
      (node (ref "U2") (pin "82") (pinfunction "PSELF_82") (pintype "passive"))
      (node (ref "U2") (pin "89") (pinfunction "G1_89") (pintype "passive"))
      (node (ref "U3") (pin "4") (pinfunction "GND_4") (pintype "passive"))
      (node (ref "U4") (pin "11") (pinfunction "G1_11") (pintype "passive"))
      (node (ref "U4") (pin "7") (pinfunction "GND_7") (pintype "passive"))
      (node (ref "U5") (pin "11") (pinfunction "G1_11") (pintype "passive"))
      (node (ref "U5") (pin "7") (pinfunction "GND_7") (pintype "passive"))
      (node (ref "U6") (pin "11") (pinfunction "G1_11") (pintype "passive"))
      (node (ref "U6") (pin "7") (pinfunction "GND_7") (pintype "passive"))
      (node (ref "U7") (pin "11") (pinfunction "G1_11") (pintype "passive"))
      (node (ref "U7") (pin "7") (pinfunction "GND_7") (pintype "passive"))
      (node (ref "U8") (pin "11") (pinfunction "G1_11") (pintype "passive"))
      (node (ref "U8") (pin "7") (pinfunction "GND_7") (pintype "passive"))
      (node (ref "USB1") (pin "10") (pinfunction "HAND2_10") (pintype "passive"))
      (node (ref "USB1") (pin "11") (pinfunction "HAND1_11") (pintype "passive"))
      (node (ref "USB1") (pin "4") (pinfunction "GND_4") (pintype "passive"))
      (node (ref "USB1") (pin "7") (pinfunction "GND_7") (pintype "passive"))
      (node (ref "USB2") (pin "4") (pinfunction "GND_4") (pintype "passive"))
      (node (ref "USB2") (pin "7") (pinfunction "GND_7") (pintype "passive"))
      (node (ref "USB2") (pin "G1") (pinfunction "HAND1_G1") (pintype "passive"))
      (node (ref "USB2") (pin "G2") (pinfunction "HAND2_G2") (pintype "passive"))
      (node (ref "USB3") (pin "4") (pinfunction "GND_4") (pintype "passive"))
      (node (ref "USB3") (pin "7") (pinfunction "GND_7") (pintype "passive"))
      (node (ref "USB3") (pin "G1") (pinfunction "HAND1_G1") (pintype "passive"))
      (node (ref "USB3") (pin "G2") (pinfunction "HAND2_G2") (pintype "passive"))
      (node (ref "USB4") (pin "4") (pinfunction "GND_4") (pintype "passive"))
      (node (ref "USB4") (pin "7") (pinfunction "GND_7") (pintype "passive"))
      (node (ref "USB4") (pin "G1") (pinfunction "HAND1_G1") (pintype "passive"))
      (node (ref "USB4") (pin "G2") (pinfunction "HAND2_G2") (pintype "passive"))
      (node (ref "USB5") (pin "4") (pinfunction "GND_4") (pintype "passive"))
      (node (ref "USB5") (pin "7") (pinfunction "GND_7") (pintype "passive"))
      (node (ref "USB5") (pin "G1") (pinfunction "HAND1_G1") (pintype "passive"))
      (node (ref "USB5") (pin "G2") (pinfunction "HAND2_G2") (pintype "passive"))
      (node (ref "Y1") (pin "2") (pinfunction "2_2") (pintype "passive"))
      (node (ref "Y1") (pin "4") (pinfunction "4_4") (pintype "passive"))
    )
    (net (code "67") (name "Net-(A1-Pad2)") (class "Default")
      (node (ref "A1") (pin "2") (pinfunction "2_2") (pintype "passive"))
      (node (ref "G1") (pin "2") (pinfunction "2_2") (pintype "passive"))
      (node (ref "R11") (pin "2") (pintype "passive"))
    )
    (net (code "68") (name "Net-(A2-Pad2)") (class "Default")
      (node (ref "A2") (pin "2") (pinfunction "2_2") (pintype "passive"))
      (node (ref "G2") (pin "2") (pinfunction "2_2") (pintype "passive"))
      (node (ref "R12") (pin "2") (pintype "passive"))
    )
    (net (code "69") (name "Net-(A3-Pad2)") (class "Default")
      (node (ref "A3") (pin "2") (pinfunction "2_2") (pintype "passive"))
      (node (ref "G3") (pin "2") (pinfunction "2_2") (pintype "passive"))
      (node (ref "R13") (pin "2") (pintype "passive"))
    )
    (net (code "70") (name "Net-(A4-Pad2)") (class "Default")
      (node (ref "A4") (pin "2") (pinfunction "2_2") (pintype "passive"))
      (node (ref "G4") (pin "2") (pinfunction "2_2") (pintype "passive"))
      (node (ref "R14") (pin "2") (pintype "passive"))
    )
    (net (code "71") (name "Net-(POW-Pad2)") (class "Default")
      (node (ref "POW") (pin "2") (pinfunction "2_2") (pintype "passive"))
      (node (ref "R15") (pin "2") (pintype "passive"))
    )
    (net (code "72") (name "Net-(U3-~{HOLD})") (class "Default")
      (node (ref "R9") (pin "1") (pintype "passive"))
      (node (ref "U3") (pin "7") (pinfunction "~{HOLD}_7") (pintype "passive"))
    )
    (net (code "73") (name "Net-(U3-~{WP})") (class "Default")
      (node (ref "R10") (pin "2") (pintype "passive"))
      (node (ref "U3") (pin "3") (pinfunction "~{WP}_3") (pintype "passive"))
    )
    (net (code "74") (name "Net-(USB2-VCC)") (class "Default")
      (node (ref "F1") (pin "2") (pinfunction "2_2") (pintype "passive"))
      (node (ref "USB2") (pin "1") (pinfunction "VCC_1") (pintype "passive"))
    )
    (net (code "75") (name "Net-(USB3-VCC)") (class "Default")
      (node (ref "F2") (pin "2") (pinfunction "2_2") (pintype "passive"))
      (node (ref "USB3") (pin "1") (pinfunction "VCC_1") (pintype "passive"))
    )
    (net (code "76") (name "Net-(USB4-VCC)") (class "Default")
      (node (ref "F3") (pin "2") (pinfunction "2_2") (pintype "passive"))
      (node (ref "USB4") (pin "1") (pinfunction "VCC_1") (pintype "passive"))
    )
    (net (code "77") (name "Net-(USB5-VCC)") (class "Default")
      (node (ref "F4") (pin "2") (pinfunction "2_2") (pintype "passive"))
      (node (ref "USB5") (pin "1") (pinfunction "VCC_1") (pintype "passive"))
    )
    (net (code "78") (name "VBUS") (class "Default")
      (node (ref "C11") (pin "2") (pintype "passive"))
      (node (ref "C25") (pin "2") (pintype "passive"))
      (node (ref "F1") (pin "1") (pinfunction "1_1") (pintype "passive"))
      (node (ref "F2") (pin "1") (pinfunction "1_1") (pintype "passive"))
      (node (ref "F3") (pin "1") (pinfunction "1_1") (pintype "passive"))
      (node (ref "F4") (pin "1") (pinfunction "1_1") (pintype "passive"))
      (node (ref "POW") (pin "1") (pinfunction "1_1") (pintype "passive"))
      (node (ref "R5") (pin "2") (pintype "passive"))
      (node (ref "R6") (pin "2") (pintype "passive"))
      (node (ref "U1") (pin "3") (pinfunction "IN_3") (pintype "passive"))
      (node (ref "U2") (pin "55") (pinfunction "VBUS_55") (pintype "passive"))
      (node (ref "U2") (pin "86") (pinfunction "V5_86") (pintype "passive"))
      (node (ref "U4") (pin "8") (pinfunction "VBUS_8") (pintype "passive"))
      (node (ref "U5") (pin "8") (pinfunction "VBUS_8") (pintype "passive"))
      (node (ref "U6") (pin "8") (pinfunction "VBUS_8") (pintype "passive"))
      (node (ref "U7") (pin "8") (pinfunction "VBUS_8") (pintype "passive"))
      (node (ref "U8") (pin "8") (pinfunction "VBUS_8") (pintype "passive"))
      (node (ref "USB1") (pin "1") (pinfunction "VCC_1") (pintype "passive"))
    )
    (net (code "79") (name "unconnected-(U2-TEST-Pad76)") (class "Default")
      (node (ref "U2") (pin "76") (pinfunction "TEST_76") (pintype "passive"))
    )
  )
)
